# TX.net
KiCad netlist of a schematic drawn in Altium Designer
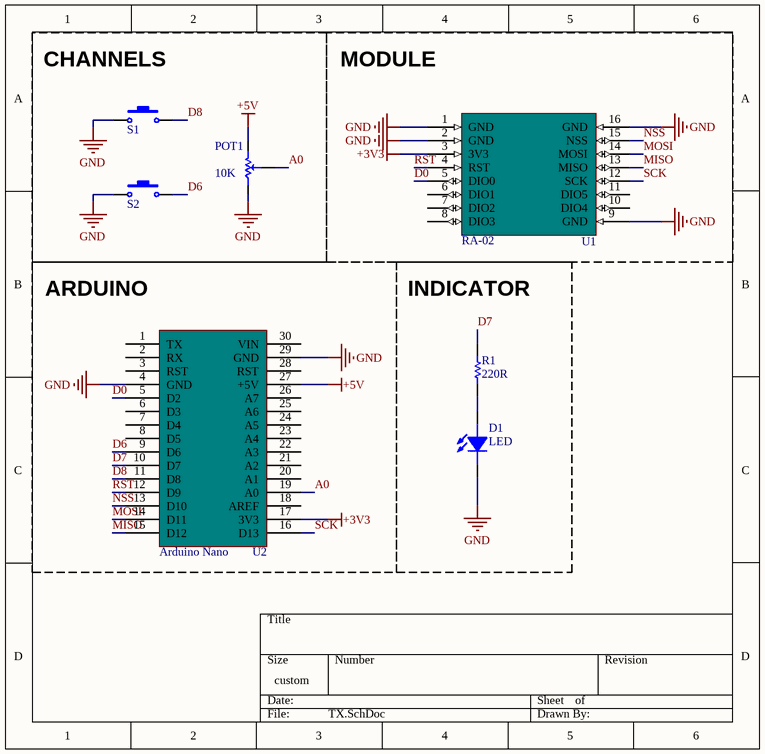
[diagram p0: TX.SchDoc]

(export (version "E")
  (design (tool "Eeschema 10.0.6"))
  (components
    (comp (ref "D1")
      (value "LED")
      (footprint "LED3mm_GRN")
      (description "Light Emitting Diode")
      (fields (field (name "DESIGNER") "Ali Hafizi"))
      (libsource (lib "Altium") (part "LED 3MM"))
    )
    (comp (ref "POT1")
      (value "10K")
      (footprint "POT")
      (description "Variable Resistor")
      (libsource (lib "Altium") (part "POT"))
    )
    (comp (ref "R1")
      (value "220R")
      (footprint "RES-(1/4)")
      (description "TOTAL DIP RESISTOR PACK")
      (fields (field (name "DESIGNER") "Ali Hafizi"))
      (libsource (lib "Altium") (part "RES DIP PACKAGE"))
    )
    (comp (ref "S1")
      (value "Switch PB")
      (footprint "Switch - Push to On")
      (description "Push Button Switch")
      (libsource (lib "Altium") (part "Switch PB"))
    )
    (comp (ref "S2")
      (value "Switch PB")
      (footprint "Switch - Push to On")
      (description "Push Button Switch")
      (libsource (lib "Altium") (part "Switch PB"))
    )
    (comp (ref "U1") (value "RA-02") (footprint "RA-02") (libsource (lib "LoRa-Ardino-Test") (part "RA-02")))
    (comp (ref "U2")
      (value "Arduino Nano")
      (footprint "Arduino_Nano328")
      (description "Arduino Nano 328")
      (libsource (lib "LoRa-Ardino-Test") (part "Arduino Nano"))
    )
  )
  (nets
    (net (code "1") (name "+3V3") (class "Default")
      (node (ref "U1") (pin "3") (pinfunction "3V3_3") (pintype "input"))
      (node (ref "U2") (pin "17") (pinfunction "3V3_17") (pintype "passive"))
    )
    (net (code "2") (name "+5V") (class "Default")
      (node (ref "POT1") (pin "2") (pinfunction "CW_2") (pintype "passive"))
      (node (ref "U2") (pin "27") (pinfunction "+5V_27") (pintype "passive"))
    )
    (net (code "3") (name "/A0") (class "Default")
      (node (ref "POT1") (pin "3") (pinfunction "SetPoint_3") (pintype "passive"))
      (node (ref "U2") (pin "19") (pinfunction "A0_19") (pintype "passive"))
    )
    (net (code "4") (name "/D0") (class "Default")
      (node (ref "U1") (pin "5") (pinfunction "DIO0_5") (pintype "bidirectional"))
      (node (ref "U2") (pin "5") (pinfunction "D2_5") (pintype "passive"))
    )
    (net (code "5") (name "/D6") (class "Default")
      (node (ref "S2") (pin "2") (pinfunction "2_2") (pintype "passive"))
      (node (ref "U2") (pin "9") (pinfunction "D6_9") (pintype "passive"))
    )
    (net (code "6") (name "/D7") (class "Default")
      (node (ref "R1") (pin "2") (pinfunction "2_2") (pintype "passive"))
      (node (ref "U2") (pin "10") (pinfunction "D7_10") (pintype "passive"))
    )
    (net (code "7") (name "/D8") (class "Default")
      (node (ref "S1") (pin "2") (pinfunction "2_2") (pintype "passive"))
      (node (ref "U2") (pin "11") (pinfunction "D8_11") (pintype "passive"))
    )
    (net (code "8") (name "/MISO") (class "Default")
      (node (ref "U1") (pin "13") (pinfunction "MISO_13") (pintype "bidirectional"))
      (node (ref "U2") (pin "15") (pinfunction "D12_15") (pintype "passive"))
    )
    (net (code "9") (name "/MOSI") (class "Default")
      (node (ref "U1") (pin "14") (pinfunction "MOSI_14") (pintype "bidirectional"))
      (node (ref "U2") (pin "14") (pinfunction "D11_14") (pintype "passive"))
    )
    (net (code "10") (name "/NSS") (class "Default")
      (node (ref "U1") (pin "15") (pinfunction "NSS_15") (pintype "bidirectional"))
      (node (ref "U2") (pin "13") (pinfunction "D10_13") (pintype "passive"))
    )
    (net (code "11") (name "/RST") (class "Default")
      (node (ref "U1") (pin "4") (pinfunction "RST_4") (pintype "input"))
      (node (ref "U2") (pin "12") (pinfunction "D9_12") (pintype "passive"))
    )
    (net (code "12") (name "/SCK") (class "Default")
      (node (ref "U1") (pin "12") (pinfunction "SCK_12") (pintype "bidirectional"))
      (node (ref "U2") (pin "16") (pinfunction "D13_16") (pintype "passive"))
    )
    (net (code "13") (name "GND") (class "Default")
      (node (ref "D1") (pin "2") (pinfunction "CATHODE_2") (pintype "passive"))
      (node (ref "POT1") (pin "1") (pinfunction "CCW_1") (pintype "passive"))
      (node (ref "S1") (pin "1") (pinfunction "1_1") (pintype "passive"))
      (node (ref "S2") (pin "1") (pinfunction "1_1") (pintype "passive"))
      (node (ref "U1") (pin "1") (pinfunction "GND_1") (pintype "input"))
      (node (ref "U1") (pin "16") (pinfunction "GND_16") (pintype "input"))
      (node (ref "U1") (pin "2") (pinfunction "GND_2") (pintype "input"))
      (node (ref "U1") (pin "9") (pinfunction "GND_9") (pintype "input"))
      (node (ref "U2") (pin "29") (pinfunction "GND_29") (pintype "passive"))
      (node (ref "U2") (pin "4") (pinfunction "GND_4") (pintype "passive"))
    )
    (net (code "14") (name "Net-(D1-ANODE)") (class "Default")
      (node (ref "D1") (pin "1") (pinfunction "ANODE_1") (pintype "passive"))
      (node (ref "R1") (pin "1") (pinfunction "1_1") (pintype "passive"))
    )
    (net (code "15") (name "unconnected-(U1-DIO1-Pad6)") (class "Default")
      (node (ref "U1") (pin "6") (pinfunction "DIO1_6") (pintype "bidirectional"))
    )
    (net (code "16") (name "unconnected-(U1-DIO2-Pad7)") (class "Default")
      (node (ref "U1") (pin "7") (pinfunction "DIO2_7") (pintype "bidirectional"))
    )
    (net (code "17") (name "unconnected-(U1-DIO3-Pad8)") (class "Default")
      (node (ref "U1") (pin "8") (pinfunction "DIO3_8") (pintype "bidirectional"))
    )
    (net (code "18") (name "unconnected-(U1-DIO4-Pad10)") (class "Default")
      (node (ref "U1") (pin "10") (pinfunction "DIO4_10") (pintype "bidirectional"))
    )
    (net (code "19") (name "unconnected-(U1-DIO5-Pad11)") (class "Default")
      (node (ref "U1") (pin "11") (pinfunction "DIO5_11") (pintype "bidirectional"))
    )
    (net (code "20") (name "unconnected-(U2-A1-Pad20)") (class "Default")
      (node (ref "U2") (pin "20") (pinfunction "A1_20") (pintype "passive"))
    )
    (net (code "21") (name "unconnected-(U2-A2-Pad21)") (class "Default")
      (node (ref "U2") (pin "21") (pinfunction "A2_21") (pintype "passive"))
    )
    (net (code "22") (name "unconnected-(U2-A3-Pad22)") (class "Default")
      (node (ref "U2") (pin "22") (pinfunction "A3_22") (pintype "passive"))
    )
    (net (code "23") (name "unconnected-(U2-A4-Pad23)") (class "Default")
      (node (ref "U2") (pin "23") (pinfunction "A4_23") (pintype "passive"))
    )
    (net (code "24") (name "unconnected-(U2-A5-Pad24)") (class "Default")
      (node (ref "U2") (pin "24") (pinfunction "A5_24") (pintype "passive"))
    )
    (net (code "25") (name "unconnected-(U2-A6-Pad25)") (class "Default")
      (node (ref "U2") (pin "25") (pinfunction "A6_25") (pintype "passive"))
    )
    (net (code "26") (name "unconnected-(U2-A7-Pad26)") (class "Default")
      (node (ref "U2") (pin "26") (pinfunction "A7_26") (pintype "passive"))
    )
    (net (code "27") (name "unconnected-(U2-AREF-Pad18)") (class "Default")
      (node (ref "U2") (pin "18") (pinfunction "AREF_18") (pintype "passive"))
    )
    (net (code "28") (name "unconnected-(U2-D3-Pad6)") (class "Default")
      (node (ref "U2") (pin "6") (pinfunction "D3_6") (pintype "passive"))
    )
    (net (code "29") (name "unconnected-(U2-D4-Pad7)") (class "Default")
      (node (ref "U2") (pin "7") (pinfunction "D4_7") (pintype "passive"))
    )
    (net (code "30") (name "unconnected-(U2-D5-Pad8)") (class "Default")
      (node (ref "U2") (pin "8") (pinfunction "D5_8") (pintype "passive"))
    )
    (net (code "31") (name "unconnected-(U2-RST-Pad3)") (class "Default")
      (node (ref "U2") (pin "3") (pinfunction "RST_3") (pintype "passive"))
    )
    (net (code "32") (name "unconnected-(U2-RST-Pad28)") (class "Default")
      (node (ref "U2") (pin "28") (pinfunction "RST_28") (pintype "passive"))
    )
    (net (code "33") (name "unconnected-(U2-RX-Pad2)") (class "Default")
      (node (ref "U2") (pin "2") (pinfunction "RX_2") (pintype "passive"))
    )
    (net (code "34") (name "unconnected-(U2-TX-Pad1)") (class "Default")
      (node (ref "U2") (pin "1") (pinfunction "TX_1") (pintype "passive"))
    )
    (net (code "35") (name "unconnected-(U2-VIN-Pad30)") (class "Default")
      (node (ref "U2") (pin "30") (pinfunction "VIN_30") (pintype "passive"))
    )
  )
)
